# plumxsodrodd.net
KiCad netlist of a schematic drawn in EAGLE
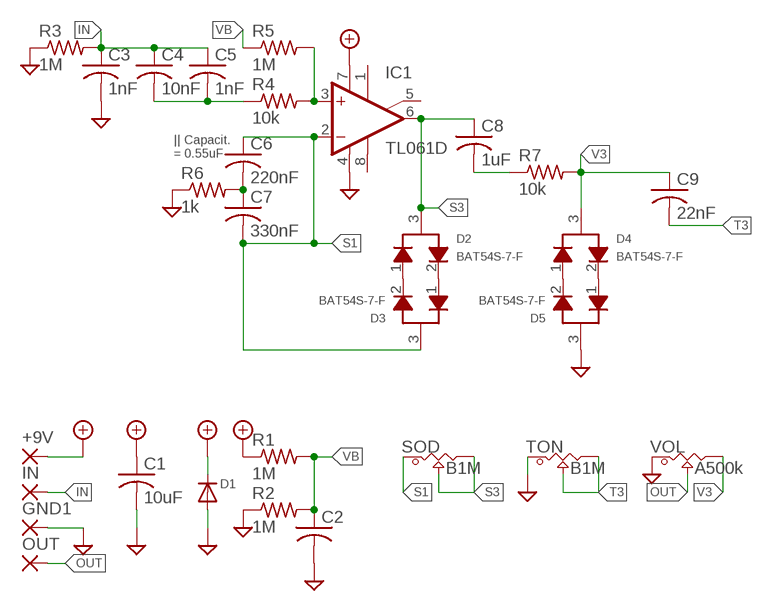
[diagram p0: schematic, sheet 1]

(export (version "E")
  (design (tool "Eeschema 10.0.6"))
  (components
    (comp (ref "+9V")
      (value "SMD2")
      (footprint "eagle-import:SMD1,27-2,54")
      (libsource (lib "eagle-import") (part "SMD2"))
    )
    (comp (ref "C1")
      (value "10uF")
      (footprint "eagle-import:C1206")
      (libsource (lib "eagle-import") (part "C-USC1206"))
    )
    (comp (ref "C2")
      (value "C-USC0603")
      (footprint "eagle-import:C0603")
      (libsource (lib "eagle-import") (part "C-USC0603"))
    )
    (comp (ref "C3")
      (value "1nF")
      (footprint "eagle-import:C0603")
      (libsource (lib "eagle-import") (part "C-USC0603"))
    )
    (comp (ref "C4")
      (value "10nF")
      (footprint "eagle-import:C0603")
      (libsource (lib "eagle-import") (part "C-USC0603"))
    )
    (comp (ref "C5")
      (value "1nF")
      (footprint "eagle-import:C0603")
      (libsource (lib "eagle-import") (part "C-USC0603"))
    )
    (comp (ref "C6")
      (value "220nF")
      (footprint "eagle-import:C0603")
      (libsource (lib "eagle-import") (part "C-USC0603"))
    )
    (comp (ref "C7")
      (value "330nF")
      (footprint "eagle-import:C0603")
      (libsource (lib "eagle-import") (part "C-USC0603"))
    )
    (comp (ref "C8")
      (value "1uF")
      (footprint "eagle-import:C0603")
      (libsource (lib "eagle-import") (part "C-USC0603"))
    )
    (comp (ref "C9")
      (value "22nF")
      (footprint "eagle-import:C0603")
      (libsource (lib "eagle-import") (part "C-USC0603"))
    )
    (comp (ref "D1")
      (value "DIODESOD-123")
      (footprint "eagle-import:SOD-123")
      (libsource (lib "eagle-import") (part "DIODESOD-123"))
    )
    (comp (ref "D2")
      (value "BAT54S-7-F")
      (footprint "eagle-import:SOT23-3")
      (fields
        (field (name "DIGIKEY_PART_NUMBER") "BAT54S-FDITR-ND")
        (field (name "MANUFACTURER") "Diodes Incorporated")
        (field (name "CREATED_BY") "PCBLayout.com")
      )
      (libsource (lib "eagle-import") (part "BAT54S-7-F"))
    )
    (comp (ref "D3")
      (value "BAT54S-7-F")
      (footprint "eagle-import:SOT23-3")
      (fields
        (field (name "DIGIKEY_PART_NUMBER") "BAT54S-FDITR-ND")
        (field (name "MANUFACTURER") "Diodes Incorporated")
        (field (name "CREATED_BY") "PCBLayout.com")
      )
      (libsource (lib "eagle-import") (part "BAT54S-7-F"))
    )
    (comp (ref "D4")
      (value "BAT54S-7-F")
      (footprint "eagle-import:SOT23-3")
      (fields
        (field (name "DIGIKEY_PART_NUMBER") "BAT54S-FDITR-ND")
        (field (name "MANUFACTURER") "Diodes Incorporated")
        (field (name "CREATED_BY") "PCBLayout.com")
      )
      (libsource (lib "eagle-import") (part "BAT54S-7-F"))
    )
    (comp (ref "D5")
      (value "BAT54S-7-F")
      (footprint "eagle-import:SOT23-3")
      (fields
        (field (name "DIGIKEY_PART_NUMBER") "BAT54S-FDITR-ND")
        (field (name "MANUFACTURER") "Diodes Incorporated")
        (field (name "CREATED_BY") "PCBLayout.com")
      )
      (libsource (lib "eagle-import") (part "BAT54S-7-F"))
    )
    (comp (ref "GND1")
      (value "SMD2")
      (footprint "eagle-import:SMD1,27-2,54")
      (libsource (lib "eagle-import") (part "SMD2"))
    )
    (comp (ref "IC1")
      (value "TL061D")
      (footprint "eagle-import:SO08")
      (libsource (lib "eagle-import") (part "TL061D"))
    )
    (comp (ref "IN")
      (value "SMD2")
      (footprint "eagle-import:SMD1,27-2,54")
      (libsource (lib "eagle-import") (part "SMD2"))
    )
    (comp (ref "OUT")
      (value "SMD2")
      (footprint "eagle-import:SMD1,27-2,54")
      (libsource (lib "eagle-import") (part "SMD2"))
    )
    (comp (ref "R1")
      (value "1M")
      (footprint "eagle-import:R0603")
      (libsource (lib "eagle-import") (part "R-US_R0603"))
    )
    (comp (ref "R2")
      (value "1M")
      (footprint "eagle-import:R0603")
      (libsource (lib "eagle-import") (part "R-US_R0603"))
    )
    (comp (ref "R3")
      (value "1M")
      (footprint "eagle-import:R0603")
      (libsource (lib "eagle-import") (part "R-US_R0603"))
    )
    (comp (ref "R4")
      (value "10k")
      (footprint "eagle-import:R0603")
      (libsource (lib "eagle-import") (part "R-US_R0603"))
    )
    (comp (ref "R5")
      (value "1M")
      (footprint "eagle-import:R0603")
      (libsource (lib "eagle-import") (part "R-US_R0603"))
    )
    (comp (ref "R6")
      (value "1k")
      (footprint "eagle-import:R0603")
      (libsource (lib "eagle-import") (part "R-US_R0603"))
    )
    (comp (ref "R7")
      (value "10k")
      (footprint "eagle-import:R0603")
      (libsource (lib "eagle-import") (part "R-US_R0603"))
    )
    (comp (ref "SOD")
      (value "B1M")
      (footprint "eagle-import:POT_9MM_SMD")
      (libsource (lib "eagle-import") (part "POT_9MM_SMD"))
    )
    (comp (ref "TON")
      (value "B1M")
      (footprint "eagle-import:POT_9MM_SMD")
      (libsource (lib "eagle-import") (part "POT_9MM_SMD"))
    )
    (comp (ref "VOL")
      (value "A500k")
      (footprint "eagle-import:POT_9MM_SMD")
      (libsource (lib "eagle-import") (part "POT_9MM_SMD"))
    )
  )
  (nets
    (net (code "1") (name "+9V") (class "Default")
      (node (ref "+9V") (pin "1") (pinfunction "P_1") (pintype "passive"))
      (node (ref "C1") (pin "1") (pinfunction "1_1") (pintype "passive"))
      (node (ref "D1") (pin "C") (pinfunction "C_C") (pintype "passive"))
      (node (ref "IC1") (pin "7") (pinfunction "V+_7") (pintype "power_in"))
      (node (ref "R1") (pin "1") (pinfunction "1_1") (pintype "passive"))
    )
    (net (code "2") (name "GND") (class "Default")
      (node (ref "C1") (pin "2") (pinfunction "2_2") (pintype "passive"))
      (node (ref "C2") (pin "2") (pinfunction "2_2") (pintype "passive"))
      (node (ref "C3") (pin "2") (pinfunction "2_2") (pintype "passive"))
      (node (ref "D1") (pin "A") (pinfunction "A_A") (pintype "passive"))
      (node (ref "D5") (pin "3") (pinfunction "3_3") (pintype "passive"))
      (node (ref "GND1") (pin "1") (pinfunction "P_1") (pintype "passive"))
      (node (ref "IC1") (pin "4") (pinfunction "V-_4") (pintype "power_in"))
      (node (ref "R2") (pin "1") (pinfunction "1_1") (pintype "passive"))
      (node (ref "R3") (pin "1") (pinfunction "1_1") (pintype "passive"))
      (node (ref "R6") (pin "1") (pinfunction "1_1") (pintype "passive"))
      (node (ref "TON") (pin "1") (pinfunction "1_1") (pintype "bidirectional"))
      (node (ref "VOL") (pin "1") (pinfunction "1_1") (pintype "bidirectional"))
    )
    (net (code "3") (name "IN") (class "Default")
      (node (ref "C3") (pin "1") (pinfunction "1_1") (pintype "passive"))
      (node (ref "C4") (pin "1") (pinfunction "1_1") (pintype "passive"))
      (node (ref "C5") (pin "1") (pinfunction "1_1") (pintype "passive"))
      (node (ref "IN") (pin "1") (pinfunction "P_1") (pintype "passive"))
      (node (ref "R3") (pin "2") (pinfunction "2_2") (pintype "passive"))
    )
    (net (code "4") (name "Net-(C4-Pad2)") (class "Default")
      (node (ref "C4") (pin "2") (pinfunction "2_2") (pintype "passive"))
      (node (ref "C5") (pin "2") (pinfunction "2_2") (pintype "passive"))
      (node (ref "R4") (pin "1") (pinfunction "1_1") (pintype "passive"))
    )
    (net (code "5") (name "Net-(C6-Pad2)") (class "Default")
      (node (ref "C6") (pin "2") (pinfunction "2_2") (pintype "passive"))
      (node (ref "C7") (pin "1") (pinfunction "1_1") (pintype "passive"))
      (node (ref "R6") (pin "2") (pinfunction "2_2") (pintype "passive"))
    )
    (net (code "6") (name "Net-(C8-Pad2)") (class "Default")
      (node (ref "C8") (pin "2") (pinfunction "2_2") (pintype "passive"))
      (node (ref "R7") (pin "1") (pinfunction "1_1") (pintype "passive"))
    )
    (net (code "7") (name "Net-(D2-Pad1)") (class "Default")
      (node (ref "D2") (pin "1") (pinfunction "1_1") (pintype "passive"))
      (node (ref "D3") (pin "2") (pinfunction "2_2") (pintype "passive"))
    )
    (net (code "8") (name "Net-(D2-Pad2)") (class "Default")
      (node (ref "D2") (pin "2") (pinfunction "2_2") (pintype "passive"))
      (node (ref "D3") (pin "1") (pinfunction "1_1") (pintype "passive"))
    )
    (net (code "9") (name "Net-(D4-Pad1)") (class "Default")
      (node (ref "D4") (pin "1") (pinfunction "1_1") (pintype "passive"))
      (node (ref "D5") (pin "2") (pinfunction "2_2") (pintype "passive"))
    )
    (net (code "10") (name "Net-(D4-Pad2)") (class "Default")
      (node (ref "D4") (pin "2") (pinfunction "2_2") (pintype "passive"))
      (node (ref "D5") (pin "1") (pinfunction "1_1") (pintype "passive"))
    )
    (net (code "11") (name "Net-(IC1-+IN)") (class "Default")
      (node (ref "IC1") (pin "3") (pinfunction "+IN_3") (pintype "input"))
      (node (ref "R4") (pin "2") (pinfunction "2_2") (pintype "passive"))
      (node (ref "R5") (pin "2") (pinfunction "2_2") (pintype "passive"))
    )
    (net (code "12") (name "OUT") (class "Default")
      (node (ref "OUT") (pin "1") (pinfunction "P_1") (pintype "passive"))
      (node (ref "VOL") (pin "2") (pinfunction "2_2") (pintype "bidirectional"))
    )
    (net (code "13") (name "S1") (class "Default")
      (node (ref "C6") (pin "1") (pinfunction "1_1") (pintype "passive"))
      (node (ref "C7") (pin "2") (pinfunction "2_2") (pintype "passive"))
      (node (ref "D3") (pin "3") (pinfunction "3_3") (pintype "passive"))
      (node (ref "IC1") (pin "2") (pinfunction "-IN_2") (pintype "input"))
      (node (ref "SOD") (pin "1") (pinfunction "1_1") (pintype "bidirectional"))
    )
    (net (code "14") (name "S3") (class "Default")
      (node (ref "C8") (pin "1") (pinfunction "1_1") (pintype "passive"))
      (node (ref "D2") (pin "3") (pinfunction "3_3") (pintype "passive"))
      (node (ref "IC1") (pin "6") (pinfunction "OUT_6") (pintype "output"))
      (node (ref "SOD") (pin "2") (pinfunction "2_2") (pintype "bidirectional"))
      (node (ref "SOD") (pin "3") (pinfunction "3_3") (pintype "bidirectional"))
    )
    (net (code "15") (name "T3") (class "Default")
      (node (ref "C9") (pin "2") (pinfunction "2_2") (pintype "passive"))
      (node (ref "TON") (pin "2") (pinfunction "2_2") (pintype "bidirectional"))
      (node (ref "TON") (pin "3") (pinfunction "3_3") (pintype "bidirectional"))
    )
    (net (code "16") (name "V3") (class "Default")
      (node (ref "C9") (pin "1") (pinfunction "1_1") (pintype "passive"))
      (node (ref "D4") (pin "3") (pinfunction "3_3") (pintype "passive"))
      (node (ref "R7") (pin "2") (pinfunction "2_2") (pintype "passive"))
      (node (ref "VOL") (pin "3") (pinfunction "3_3") (pintype "bidirectional"))
    )
    (net (code "17") (name "VB") (class "Default")
      (node (ref "C2") (pin "1") (pinfunction "1_1") (pintype "passive"))
      (node (ref "R1") (pin "2") (pinfunction "2_2") (pintype "passive"))
      (node (ref "R2") (pin "2") (pinfunction "2_2") (pintype "passive"))
      (node (ref "R5") (pin "1") (pinfunction "1_1") (pintype "passive"))
    )
    (net (code "18") (name "unconnected-(IC1-ON1-Pad1)") (class "Default")
      (node (ref "IC1") (pin "1") (pinfunction "ON1_1") (pintype "passive"))
    )
    (net (code "19") (name "unconnected-(IC1-ON2-Pad5)") (class "Default")
      (node (ref "IC1") (pin "5") (pinfunction "ON2_5") (pintype "passive"))
    )
    (net (code "20") (name "unconnected-(IC1-OPT-Pad8)") (class "Default")
      (node (ref "IC1") (pin "8") (pinfunction "OPT_8") (pintype "passive"))
    )
  )
)
